# Main_Board.net
KiCad netlist of a schematic drawn in EAGLE
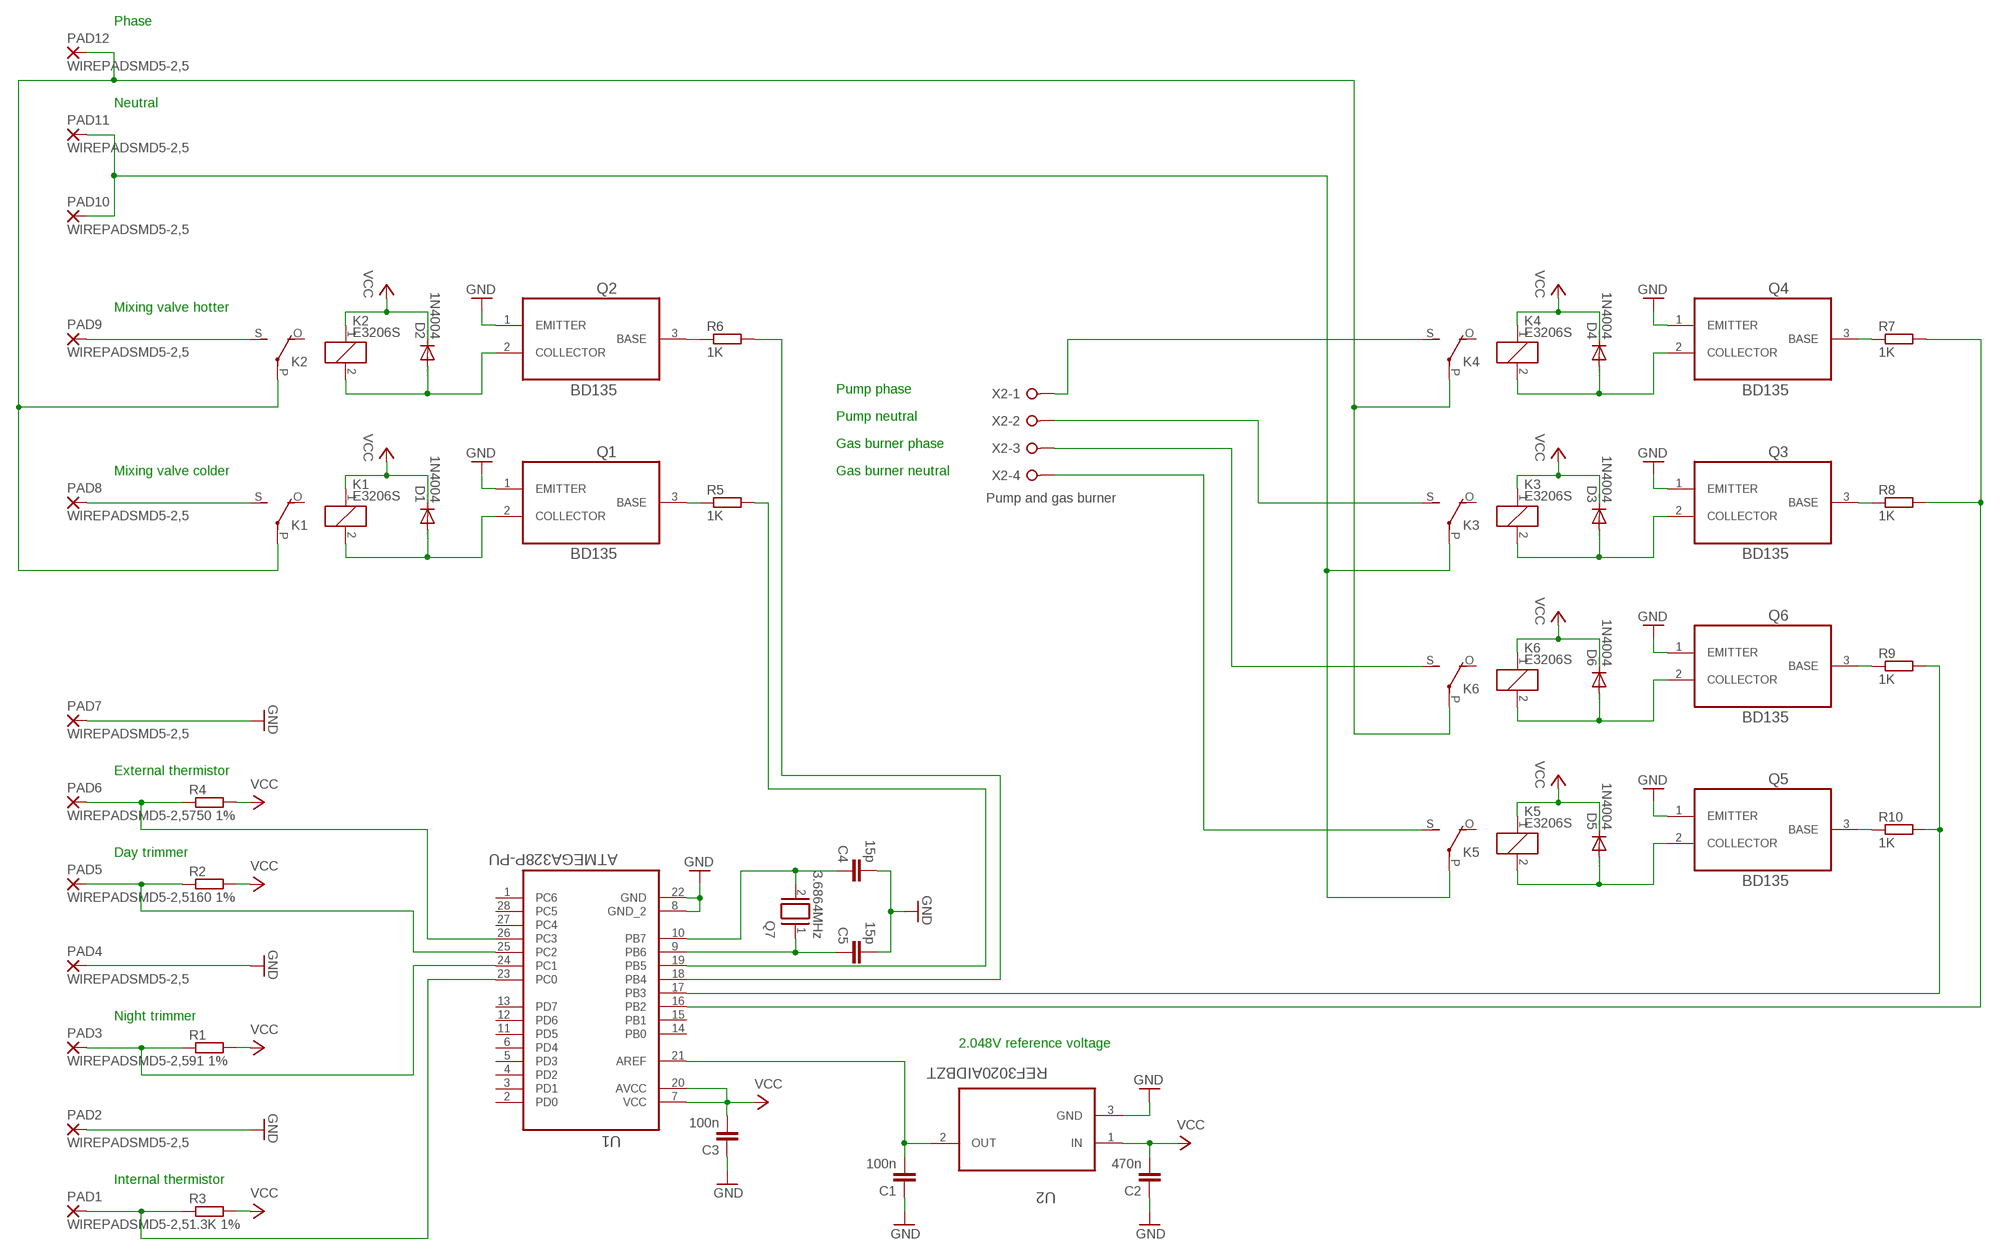
[diagram p0: schematic, sheet 1]

(export (version "E")
  (design (tool "Eeschema 10.0.6"))
  (components
    (comp (ref "C1")
      (value "100n")
      (footprint "eagle-import:C050-035X075")
      (libsource (lib "eagle-import") (part "C-EU050-035X075"))
    )
    (comp (ref "C2")
      (value "470n")
      (footprint "eagle-import:C050-035X075")
      (libsource (lib "eagle-import") (part "C-EU050-035X075"))
    )
    (comp (ref "C3")
      (value "100n")
      (footprint "eagle-import:C050-035X075")
      (libsource (lib "eagle-import") (part "C-EU050-035X075"))
    )
    (comp (ref "C4")
      (value "15p")
      (footprint "eagle-import:C025-030X050")
      (libsource (lib "eagle-import") (part "C-EU025-030X050"))
    )
    (comp (ref "C5")
      (value "15p")
      (footprint "eagle-import:C025-030X050")
      (libsource (lib "eagle-import") (part "C-EU025-030X050"))
    )
    (comp (ref "D1")
      (value "1N4004")
      (footprint "eagle-import:DO41-10")
      (libsource (lib "eagle-import") (part "1N4004"))
    )
    (comp (ref "D2")
      (value "1N4004")
      (footprint "eagle-import:DO41-10")
      (libsource (lib "eagle-import") (part "1N4004"))
    )
    (comp (ref "D3")
      (value "1N4004")
      (footprint "eagle-import:DO41-10")
      (libsource (lib "eagle-import") (part "1N4004"))
    )
    (comp (ref "D4")
      (value "1N4004")
      (footprint "eagle-import:DO41-10")
      (libsource (lib "eagle-import") (part "1N4004"))
    )
    (comp (ref "D5")
      (value "1N4004")
      (footprint "eagle-import:DO41-10")
      (libsource (lib "eagle-import") (part "1N4004"))
    )
    (comp (ref "D6")
      (value "1N4004")
      (footprint "eagle-import:DO41-10")
      (libsource (lib "eagle-import") (part "1N4004"))
    )
    (comp (ref "K1")
      (value "E3206S")
      (footprint "eagle-import:E3206S")
      (libsource (lib "eagle-import") (part "E3206S"))
    )
    (comp (ref "K2")
      (value "E3206S")
      (footprint "eagle-import:E3206S")
      (libsource (lib "eagle-import") (part "E3206S"))
    )
    (comp (ref "K3")
      (value "E3206S")
      (footprint "eagle-import:E3206S")
      (libsource (lib "eagle-import") (part "E3206S"))
    )
    (comp (ref "K4")
      (value "E3206S")
      (footprint "eagle-import:E3206S")
      (libsource (lib "eagle-import") (part "E3206S"))
    )
    (comp (ref "K5")
      (value "E3206S")
      (footprint "eagle-import:E3206S")
      (libsource (lib "eagle-import") (part "E3206S"))
    )
    (comp (ref "K6")
      (value "E3206S")
      (footprint "eagle-import:E3206S")
      (libsource (lib "eagle-import") (part "E3206S"))
    )
    (comp (ref "PAD1")
      (value "WIREPADSMD5-2,5")
      (footprint "eagle-import:5-2,5")
      (libsource (lib "eagle-import") (part "WIREPADSMD5-2,5"))
    )
    (comp (ref "PAD2")
      (value "WIREPADSMD5-2,5")
      (footprint "eagle-import:5-2,5")
      (libsource (lib "eagle-import") (part "WIREPADSMD5-2,5"))
    )
    (comp (ref "PAD3")
      (value "WIREPADSMD5-2,5")
      (footprint "eagle-import:5-2,5")
      (libsource (lib "eagle-import") (part "WIREPADSMD5-2,5"))
    )
    (comp (ref "PAD4")
      (value "WIREPADSMD5-2,5")
      (footprint "eagle-import:5-2,5")
      (libsource (lib "eagle-import") (part "WIREPADSMD5-2,5"))
    )
    (comp (ref "PAD5")
      (value "WIREPADSMD5-2,5")
      (footprint "eagle-import:5-2,5")
      (libsource (lib "eagle-import") (part "WIREPADSMD5-2,5"))
    )
    (comp (ref "PAD6")
      (value "WIREPADSMD5-2,5")
      (footprint "eagle-import:5-2,5")
      (libsource (lib "eagle-import") (part "WIREPADSMD5-2,5"))
    )
    (comp (ref "PAD7")
      (value "WIREPADSMD5-2,5")
      (footprint "eagle-import:5-2,5")
      (libsource (lib "eagle-import") (part "WIREPADSMD5-2,5"))
    )
    (comp (ref "PAD8")
      (value "WIREPADSMD5-2,5")
      (footprint "eagle-import:5-2,5")
      (libsource (lib "eagle-import") (part "WIREPADSMD5-2,5"))
    )
    (comp (ref "PAD9")
      (value "WIREPADSMD5-2,5")
      (footprint "eagle-import:5-2,5")
      (libsource (lib "eagle-import") (part "WIREPADSMD5-2,5"))
    )
    (comp (ref "PAD10")
      (value "WIREPADSMD5-2,5")
      (footprint "eagle-import:5-2,5")
      (libsource (lib "eagle-import") (part "WIREPADSMD5-2,5"))
    )
    (comp (ref "PAD11")
      (value "WIREPADSMD5-2,5")
      (footprint "eagle-import:5-2,5")
      (libsource (lib "eagle-import") (part "WIREPADSMD5-2,5"))
    )
    (comp (ref "PAD12")
      (value "WIREPADSMD5-2,5")
      (footprint "eagle-import:5-2,5")
      (libsource (lib "eagle-import") (part "WIREPADSMD5-2,5"))
    )
    (comp (ref "Q1")
      (value "BD135")
      (footprint "eagle-import:TRANS_BD135")
      (fields (field (name "MPN") "    BD135"))
      (libsource (lib "eagle-import") (part "BD135"))
    )
    (comp (ref "Q2")
      (value "BD135")
      (footprint "eagle-import:TRANS_BD135")
      (fields (field (name "MPN") "    BD135"))
      (libsource (lib "eagle-import") (part "BD135"))
    )
    (comp (ref "Q3")
      (value "BD135")
      (footprint "eagle-import:TRANS_BD135")
      (fields (field (name "MPN") "    BD135"))
      (libsource (lib "eagle-import") (part "BD135"))
    )
    (comp (ref "Q4")
      (value "BD135")
      (footprint "eagle-import:TRANS_BD135")
      (fields (field (name "MPN") "    BD135"))
      (libsource (lib "eagle-import") (part "BD135"))
    )
    (comp (ref "Q5")
      (value "BD135")
      (footprint "eagle-import:TRANS_BD135")
      (fields (field (name "MPN") "    BD135"))
      (libsource (lib "eagle-import") (part "BD135"))
    )
    (comp (ref "Q6")
      (value "BD135")
      (footprint "eagle-import:TRANS_BD135")
      (fields (field (name "MPN") "    BD135"))
      (libsource (lib "eagle-import") (part "BD135"))
    )
    (comp (ref "Q7")
      (value "3.6864MHz")
      (footprint "eagle-import:QS")
      (libsource (lib "eagle-import") (part "XTAL/S"))
    )
    (comp (ref "R1")
      (value "91 1%")
      (footprint "eagle-import:0207_10")
      (libsource (lib "eagle-import") (part "R-EU_0207/10"))
    )
    (comp (ref "R2")
      (value "160 1%")
      (footprint "eagle-import:0207_10")
      (libsource (lib "eagle-import") (part "R-EU_0207/10"))
    )
    (comp (ref "R3")
      (value "1.3K 1%")
      (footprint "eagle-import:0207_10")
      (libsource (lib "eagle-import") (part "R-EU_0207/10"))
    )
    (comp (ref "R4")
      (value "750 1%")
      (footprint "eagle-import:0207_10")
      (libsource (lib "eagle-import") (part "R-EU_0207/10"))
    )
    (comp (ref "R5")
      (value "1K")
      (footprint "eagle-import:0207_10")
      (libsource (lib "eagle-import") (part "R-EU_0207/10"))
    )
    (comp (ref "R6")
      (value "1K")
      (footprint "eagle-import:0207_10")
      (libsource (lib "eagle-import") (part "R-EU_0207/10"))
    )
    (comp (ref "R7")
      (value "1K")
      (footprint "eagle-import:0207_10")
      (libsource (lib "eagle-import") (part "R-EU_0207/10"))
    )
    (comp (ref "R8")
      (value "1K")
      (footprint "eagle-import:0207_10")
      (libsource (lib "eagle-import") (part "R-EU_0207/10"))
    )
    (comp (ref "R9")
      (value "1K")
      (footprint "eagle-import:0207_10")
      (libsource (lib "eagle-import") (part "R-EU_0207/10"))
    )
    (comp (ref "R10")
      (value "1K")
      (footprint "eagle-import:0207_10")
      (libsource (lib "eagle-import") (part "R-EU_0207/10"))
    )
    (comp (ref "U1")
      (value "ATMEGA328P-PU")
      (footprint "eagle-import:DIP254P762X457-28")
      (libsource (lib "eagle-import") (part "ATMEGA328P-PU"))
    )
    (comp (ref "U2")
      (value "REF3020AIDBZT")
      (footprint "eagle-import:SOT95P237X112-3N")
      (libsource (lib "eagle-import") (part "REF3020AIDBZT"))
    )
    (comp (ref "X2")
      (value "Pump and gas burner")
      (footprint "eagle-import:W237-4P")
      (libsource (lib "eagle-import") (part "W237-04P"))
    )
  )
  (nets
    (net (code "1") (name "GND") (class "Default")
      (node (ref "C1") (pin "1") (pinfunction "1_1") (pintype "passive"))
      (node (ref "C2") (pin "1") (pinfunction "1_1") (pintype "passive"))
      (node (ref "C3") (pin "1") (pinfunction "1_1") (pintype "passive"))
      (node (ref "C4") (pin "2") (pinfunction "2_2") (pintype "passive"))
      (node (ref "C5") (pin "2") (pinfunction "2_2") (pintype "passive"))
      (node (ref "PAD2") (pin "1") (pinfunction "P_1") (pintype "passive"))
      (node (ref "PAD4") (pin "1") (pinfunction "P_1") (pintype "passive"))
      (node (ref "PAD7") (pin "1") (pinfunction "P_1") (pintype "passive"))
      (node (ref "Q1") (pin "1") (pinfunction "EMITTER_1") (pintype "passive"))
      (node (ref "Q2") (pin "1") (pinfunction "EMITTER_1") (pintype "passive"))
      (node (ref "Q3") (pin "1") (pinfunction "EMITTER_1") (pintype "passive"))
      (node (ref "Q4") (pin "1") (pinfunction "EMITTER_1") (pintype "passive"))
      (node (ref "Q5") (pin "1") (pinfunction "EMITTER_1") (pintype "passive"))
      (node (ref "Q6") (pin "1") (pinfunction "EMITTER_1") (pintype "passive"))
      (node (ref "U1") (pin "22") (pinfunction "GND_22") (pintype "passive"))
      (node (ref "U1") (pin "8") (pinfunction "GND_2_8") (pintype "passive"))
      (node (ref "U2") (pin "3") (pinfunction "GND_3") (pintype "passive"))
    )
    (net (code "2") (name "Net-(PAD1-P)") (class "Default")
      (node (ref "PAD1") (pin "1") (pinfunction "P_1") (pintype "passive"))
      (node (ref "R3") (pin "1") (pinfunction "1_1") (pintype "passive"))
      (node (ref "U1") (pin "23") (pinfunction "PC0_23") (pintype "bidirectional"))
    )
    (net (code "3") (name "Net-(PAD3-P)") (class "Default")
      (node (ref "PAD3") (pin "1") (pinfunction "P_1") (pintype "passive"))
      (node (ref "R1") (pin "1") (pinfunction "1_1") (pintype "passive"))
      (node (ref "U1") (pin "24") (pinfunction "PC1_24") (pintype "bidirectional"))
    )
    (net (code "4") (name "Net-(PAD5-P)") (class "Default")
      (node (ref "PAD5") (pin "1") (pinfunction "P_1") (pintype "passive"))
      (node (ref "R2") (pin "1") (pinfunction "1_1") (pintype "passive"))
      (node (ref "U1") (pin "25") (pinfunction "PC2_25") (pintype "bidirectional"))
    )
    (net (code "5") (name "Net-(PAD6-P)") (class "Default")
      (node (ref "PAD6") (pin "1") (pinfunction "P_1") (pintype "passive"))
      (node (ref "R4") (pin "1") (pinfunction "1_1") (pintype "passive"))
      (node (ref "U1") (pin "26") (pinfunction "PC3_26") (pintype "bidirectional"))
    )
    (net (code "6") (name "Net-(PAD8-P)") (class "Default")
      (node (ref "K1") (pin "S") (pinfunction "S_S") (pintype "passive"))
      (node (ref "PAD8") (pin "1") (pinfunction "P_1") (pintype "passive"))
    )
    (net (code "7") (name "Net-(PAD9-P)") (class "Default")
      (node (ref "K2") (pin "S") (pinfunction "S_S") (pintype "passive"))
      (node (ref "PAD9") (pin "1") (pinfunction "P_1") (pintype "passive"))
    )
    (net (code "8") (name "Net-(PAD10-P)") (class "Default")
      (node (ref "K3") (pin "P") (pinfunction "P_P") (pintype "passive"))
      (node (ref "K5") (pin "P") (pinfunction "P_P") (pintype "passive"))
      (node (ref "PAD10") (pin "1") (pinfunction "P_1") (pintype "passive"))
      (node (ref "PAD11") (pin "1") (pinfunction "P_1") (pintype "passive"))
    )
    (net (code "9") (name "Net-(PAD12-P)") (class "Default")
      (node (ref "K1") (pin "P") (pinfunction "P_P") (pintype "passive"))
      (node (ref "K2") (pin "P") (pinfunction "P_P") (pintype "passive"))
      (node (ref "K4") (pin "P") (pinfunction "P_P") (pintype "passive"))
      (node (ref "K6") (pin "P") (pinfunction "P_P") (pintype "passive"))
      (node (ref "PAD12") (pin "1") (pinfunction "P_1") (pintype "passive"))
    )
    (net (code "10") (name "Net-(Q1-BASE)") (class "Default")
      (node (ref "Q1") (pin "3") (pinfunction "BASE_3") (pintype "passive"))
      (node (ref "R5") (pin "1") (pinfunction "1_1") (pintype "passive"))
    )
    (net (code "11") (name "Net-(Q1-COLLECTOR)") (class "Default")
      (node (ref "D1") (pin "A") (pinfunction "A_A") (pintype "passive"))
      (node (ref "K1") (pin "2") (pinfunction "2_2") (pintype "passive"))
      (node (ref "Q1") (pin "2") (pinfunction "COLLECTOR_2") (pintype "passive"))
    )
    (net (code "12") (name "Net-(Q2-BASE)") (class "Default")
      (node (ref "Q2") (pin "3") (pinfunction "BASE_3") (pintype "passive"))
      (node (ref "R6") (pin "1") (pinfunction "1_1") (pintype "passive"))
    )
    (net (code "13") (name "Net-(Q2-COLLECTOR)") (class "Default")
      (node (ref "D2") (pin "A") (pinfunction "A_A") (pintype "passive"))
      (node (ref "K2") (pin "2") (pinfunction "2_2") (pintype "passive"))
      (node (ref "Q2") (pin "2") (pinfunction "COLLECTOR_2") (pintype "passive"))
    )
    (net (code "14") (name "Net-(Q3-BASE)") (class "Default")
      (node (ref "Q3") (pin "3") (pinfunction "BASE_3") (pintype "passive"))
      (node (ref "R8") (pin "1") (pinfunction "1_1") (pintype "passive"))
    )
    (net (code "15") (name "Net-(Q3-COLLECTOR)") (class "Default")
      (node (ref "D3") (pin "A") (pinfunction "A_A") (pintype "passive"))
      (node (ref "K3") (pin "2") (pinfunction "2_2") (pintype "passive"))
      (node (ref "Q3") (pin "2") (pinfunction "COLLECTOR_2") (pintype "passive"))
    )
    (net (code "16") (name "Net-(Q4-BASE)") (class "Default")
      (node (ref "Q4") (pin "3") (pinfunction "BASE_3") (pintype "passive"))
      (node (ref "R7") (pin "1") (pinfunction "1_1") (pintype "passive"))
    )
    (net (code "17") (name "Net-(Q4-COLLECTOR)") (class "Default")
      (node (ref "D4") (pin "A") (pinfunction "A_A") (pintype "passive"))
      (node (ref "K4") (pin "2") (pinfunction "2_2") (pintype "passive"))
      (node (ref "Q4") (pin "2") (pinfunction "COLLECTOR_2") (pintype "passive"))
    )
    (net (code "18") (name "Net-(Q5-BASE)") (class "Default")
      (node (ref "Q5") (pin "3") (pinfunction "BASE_3") (pintype "passive"))
      (node (ref "R10") (pin "1") (pinfunction "1_1") (pintype "passive"))
    )
    (net (code "19") (name "Net-(Q5-COLLECTOR)") (class "Default")
      (node (ref "D5") (pin "A") (pinfunction "A_A") (pintype "passive"))
      (node (ref "K5") (pin "2") (pinfunction "2_2") (pintype "passive"))
      (node (ref "Q5") (pin "2") (pinfunction "COLLECTOR_2") (pintype "passive"))
    )
    (net (code "20") (name "Net-(Q6-BASE)") (class "Default")
      (node (ref "Q6") (pin "3") (pinfunction "BASE_3") (pintype "passive"))
      (node (ref "R9") (pin "1") (pinfunction "1_1") (pintype "passive"))
    )
    (net (code "21") (name "Net-(Q6-COLLECTOR)") (class "Default")
      (node (ref "D6") (pin "A") (pinfunction "A_A") (pintype "passive"))
      (node (ref "K6") (pin "2") (pinfunction "2_2") (pintype "passive"))
      (node (ref "Q6") (pin "2") (pinfunction "COLLECTOR_2") (pintype "passive"))
    )
    (net (code "22") (name "Net-(U1-AREF)") (class "Default")
      (node (ref "C1") (pin "2") (pinfunction "2_2") (pintype "passive"))
      (node (ref "U1") (pin "21") (pinfunction "AREF_21") (pintype "input"))
      (node (ref "U2") (pin "2") (pinfunction "OUT_2") (pintype "output"))
    )
    (net (code "23") (name "Net-(U1-PB2)") (class "Default")
      (node (ref "R7") (pin "2") (pinfunction "2_2") (pintype "passive"))
      (node (ref "R8") (pin "2") (pinfunction "2_2") (pintype "passive"))
      (node (ref "U1") (pin "16") (pinfunction "PB2_16") (pintype "bidirectional"))
    )
    (net (code "24") (name "Net-(U1-PB3)") (class "Default")
      (node (ref "R10") (pin "2") (pinfunction "2_2") (pintype "passive"))
      (node (ref "R9") (pin "2") (pinfunction "2_2") (pintype "passive"))
      (node (ref "U1") (pin "17") (pinfunction "PB3_17") (pintype "bidirectional"))
    )
    (net (code "25") (name "Net-(U1-PB4)") (class "Default")
      (node (ref "R6") (pin "2") (pinfunction "2_2") (pintype "passive"))
      (node (ref "U1") (pin "18") (pinfunction "PB4_18") (pintype "bidirectional"))
    )
    (net (code "26") (name "Net-(U1-PB5)") (class "Default")
      (node (ref "R5") (pin "2") (pinfunction "2_2") (pintype "passive"))
      (node (ref "U1") (pin "19") (pinfunction "PB5_19") (pintype "bidirectional"))
    )
    (net (code "27") (name "Net-(U1-PB6)") (class "Default")
      (node (ref "C5") (pin "1") (pinfunction "1_1") (pintype "passive"))
      (node (ref "Q7") (pin "1") (pinfunction "1_1") (pintype "passive"))
      (node (ref "U1") (pin "9") (pinfunction "PB6_9") (pintype "bidirectional"))
    )
    (net (code "28") (name "Net-(U1-PB7)") (class "Default")
      (node (ref "C4") (pin "1") (pinfunction "1_1") (pintype "passive"))
      (node (ref "Q7") (pin "2") (pinfunction "2_2") (pintype "passive"))
      (node (ref "U1") (pin "10") (pinfunction "PB7_10") (pintype "bidirectional"))
    )
    (net (code "29") (name "Net-(X2A-KL)") (class "Default")
      (node (ref "K4") (pin "S") (pinfunction "S_S") (pintype "passive"))
      (node (ref "X2") (pin "1") (pinfunction "KL_1") (pintype "passive"))
    )
    (net (code "30") (name "Net-(X2B-KL)") (class "Default")
      (node (ref "K3") (pin "S") (pinfunction "S_S") (pintype "passive"))
      (node (ref "X2") (pin "2") (pinfunction "KL_2") (pintype "passive"))
    )
    (net (code "31") (name "Net-(X2C-KL)") (class "Default")
      (node (ref "K6") (pin "S") (pinfunction "S_S") (pintype "passive"))
      (node (ref "X2") (pin "3") (pinfunction "KL_3") (pintype "passive"))
    )
    (net (code "32") (name "Net-(X2D-KL)") (class "Default")
      (node (ref "K5") (pin "S") (pinfunction "S_S") (pintype "passive"))
      (node (ref "X2") (pin "4") (pinfunction "KL_4") (pintype "passive"))
    )
    (net (code "33") (name "VCC") (class "Default")
      (node (ref "C2") (pin "2") (pinfunction "2_2") (pintype "passive"))
      (node (ref "C3") (pin "2") (pinfunction "2_2") (pintype "passive"))
      (node (ref "D1") (pin "C") (pinfunction "C_C") (pintype "passive"))
      (node (ref "D2") (pin "C") (pinfunction "C_C") (pintype "passive"))
      (node (ref "D3") (pin "C") (pinfunction "C_C") (pintype "passive"))
      (node (ref "D4") (pin "C") (pinfunction "C_C") (pintype "passive"))
      (node (ref "D5") (pin "C") (pinfunction "C_C") (pintype "passive"))
      (node (ref "D6") (pin "C") (pinfunction "C_C") (pintype "passive"))
      (node (ref "K1") (pin "1") (pinfunction "1_1") (pintype "passive"))
      (node (ref "K2") (pin "1") (pinfunction "1_1") (pintype "passive"))
      (node (ref "K3") (pin "1") (pinfunction "1_1") (pintype "passive"))
      (node (ref "K4") (pin "1") (pinfunction "1_1") (pintype "passive"))
      (node (ref "K5") (pin "1") (pinfunction "1_1") (pintype "passive"))
      (node (ref "K6") (pin "1") (pinfunction "1_1") (pintype "passive"))
      (node (ref "R1") (pin "2") (pinfunction "2_2") (pintype "passive"))
      (node (ref "R2") (pin "2") (pinfunction "2_2") (pintype "passive"))
      (node (ref "R3") (pin "2") (pinfunction "2_2") (pintype "passive"))
      (node (ref "R4") (pin "2") (pinfunction "2_2") (pintype "passive"))
      (node (ref "U1") (pin "20") (pinfunction "AVCC_20") (pintype "power_in"))
      (node (ref "U1") (pin "7") (pinfunction "VCC_7") (pintype "power_in"))
      (node (ref "U2") (pin "1") (pinfunction "IN_1") (pintype "power_in"))
    )
    (net (code "34") (name "unconnected-(K1-PadO)") (class "Default")
      (node (ref "K1") (pin "O") (pinfunction "O_O") (pintype "passive"))
    )
    (net (code "35") (name "unconnected-(K2-PadO)") (class "Default")
      (node (ref "K2") (pin "O") (pinfunction "O_O") (pintype "passive"))
    )
    (net (code "36") (name "unconnected-(K3-PadO)") (class "Default")
      (node (ref "K3") (pin "O") (pinfunction "O_O") (pintype "passive"))
    )
    (net (code "37") (name "unconnected-(K4-PadO)") (class "Default")
      (node (ref "K4") (pin "O") (pinfunction "O_O") (pintype "passive"))
    )
    (net (code "38") (name "unconnected-(K5-PadO)") (class "Default")
      (node (ref "K5") (pin "O") (pinfunction "O_O") (pintype "passive"))
    )
    (net (code "39") (name "unconnected-(K6-PadO)") (class "Default")
      (node (ref "K6") (pin "O") (pinfunction "O_O") (pintype "passive"))
    )
    (net (code "40") (name "unconnected-(U1-PB0-Pad14)") (class "Default")
      (node (ref "U1") (pin "14") (pinfunction "PB0_14") (pintype "bidirectional"))
    )
    (net (code "41") (name "unconnected-(U1-PB1-Pad15)") (class "Default")
      (node (ref "U1") (pin "15") (pinfunction "PB1_15") (pintype "bidirectional"))
    )
    (net (code "42") (name "unconnected-(U1-PC4-Pad27)") (class "Default")
      (node (ref "U1") (pin "27") (pinfunction "PC4_27") (pintype "bidirectional"))
    )
    (net (code "43") (name "unconnected-(U1-PC5-Pad28)") (class "Default")
      (node (ref "U1") (pin "28") (pinfunction "PC5_28") (pintype "bidirectional"))
    )
    (net (code "44") (name "unconnected-(U1-PC6-Pad1)") (class "Default")
      (node (ref "U1") (pin "1") (pinfunction "PC6_1") (pintype "bidirectional"))
    )
    (net (code "45") (name "unconnected-(U1-PD0-Pad2)") (class "Default")
      (node (ref "U1") (pin "2") (pinfunction "PD0_2") (pintype "bidirectional"))
    )
    (net (code "46") (name "unconnected-(U1-PD1-Pad3)") (class "Default")
      (node (ref "U1") (pin "3") (pinfunction "PD1_3") (pintype "bidirectional"))
    )
    (net (code "47") (name "unconnected-(U1-PD2-Pad4)") (class "Default")
      (node (ref "U1") (pin "4") (pinfunction "PD2_4") (pintype "bidirectional"))
    )
    (net (code "48") (name "unconnected-(U1-PD3-Pad5)") (class "Default")
      (node (ref "U1") (pin "5") (pinfunction "PD3_5") (pintype "bidirectional"))
    )
    (net (code "49") (name "unconnected-(U1-PD4-Pad6)") (class "Default")
      (node (ref "U1") (pin "6") (pinfunction "PD4_6") (pintype "bidirectional"))
    )
    (net (code "50") (name "unconnected-(U1-PD5-Pad11)") (class "Default")
      (node (ref "U1") (pin "11") (pinfunction "PD5_11") (pintype "bidirectional"))
    )
    (net (code "51") (name "unconnected-(U1-PD6-Pad12)") (class "Default")
      (node (ref "U1") (pin "12") (pinfunction "PD6_12") (pintype "bidirectional"))
    )
    (net (code "52") (name "unconnected-(U1-PD7-Pad13)") (class "Default")
      (node (ref "U1") (pin "13") (pinfunction "PD7_13") (pintype "bidirectional"))
    )
  )
)
